# PWM_OUTPUT.net
KiCad netlist of a schematic drawn in Altium Designer
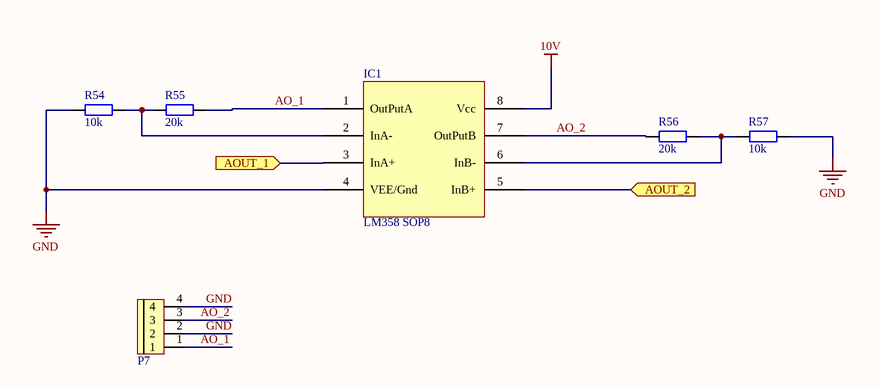
[diagram p0: PWM_OUTPUT.SchDoc]

(export (version "E")
  (design (tool "Eeschema 10.0.6"))
  (components
    (comp (ref "IC1")
      (value "LM358 SOP8")
      (footprint "SOP 8")
      (description "Dán")
      (libsource (lib "Altium_Lib_by_KhueNguyenCreator") (part "LM358 SOP8"))
    )
    (comp (ref "P7")
      (value "CON 4 EDG5.08")
      (footprint "CON 4 4EDG5.08")
      (description "Cắm")
      (libsource (lib "Altium_Lib_by_KhueNguyenCreator") (part "CON 4 EDG5.08"))
    )
    (comp (ref "R54")
      (value "10k")
      (footprint "tro smd 0805")
      (description "Dán")
      (libsource (lib "Altium_Lib_by_KhueNguyenCreator") (part "Tro 0805 5% 10k"))
    )
    (comp (ref "R55")
      (value "20k")
      (footprint "tro smd 0805")
      (description "Dán")
      (libsource (lib "Altium_Lib_by_KhueNguyenCreator") (part "Tro 0805 5% 20k"))
    )
    (comp (ref "R56")
      (value "20k")
      (footprint "tro smd 0805")
      (description "Dán")
      (libsource (lib "Altium_Lib_by_KhueNguyenCreator") (part "Tro 0805 5% 20k"))
    )
    (comp (ref "R57")
      (value "10k")
      (footprint "tro smd 0805")
      (description "Dán")
      (libsource (lib "Altium_Lib_by_KhueNguyenCreator") (part "Tro 0805 5% 10k"))
    )
  )
  (nets
    (net (code "1") (name "/AOUT_1") (class "Default")
      (node (ref "IC1") (pin "3") (pinfunction "InA+_3") (pintype "passive"))
    )
    (net (code "2") (name "/AOUT_2") (class "Default")
      (node (ref "IC1") (pin "5") (pinfunction "InB+_5") (pintype "passive"))
    )
    (net (code "3") (name "/AO_1") (class "Default")
      (node (ref "IC1") (pin "1") (pinfunction "OutPutA_1") (pintype "passive"))
      (node (ref "P7") (pin "1") (pinfunction "1_1") (pintype "passive"))
      (node (ref "R55") (pin "2") (pinfunction "2_2") (pintype "passive"))
    )
    (net (code "4") (name "/AO_2") (class "Default")
      (node (ref "IC1") (pin "7") (pinfunction "OutPutB_7") (pintype "passive"))
      (node (ref "P7") (pin "3") (pinfunction "3_3") (pintype "passive"))
      (node (ref "R56") (pin "1") (pinfunction "1_1") (pintype "passive"))
    )
    (net (code "5") (name "10V") (class "Default")
      (node (ref "IC1") (pin "8") (pinfunction "Vcc_8") (pintype "passive"))
    )
    (net (code "6") (name "GND") (class "Default")
      (node (ref "IC1") (pin "4") (pinfunction "VEE/Gnd_4") (pintype "passive"))
      (node (ref "P7") (pin "2") (pinfunction "2_2") (pintype "passive"))
      (node (ref "P7") (pin "4") (pinfunction "4_4") (pintype "passive"))
      (node (ref "R54") (pin "1") (pinfunction "1_1") (pintype "passive"))
      (node (ref "R57") (pin "2") (pinfunction "2_2") (pintype "passive"))
    )
    (net (code "7") (name "Net-(IC1-InA-)") (class "Default")
      (node (ref "IC1") (pin "2") (pinfunction "InA-_2") (pintype "passive"))
      (node (ref "R54") (pin "2") (pinfunction "2_2") (pintype "passive"))
      (node (ref "R55") (pin "1") (pinfunction "1_1") (pintype "passive"))
    )
    (net (code "8") (name "Net-(IC1-InB-)") (class "Default")
      (node (ref "IC1") (pin "6") (pinfunction "InB-_6") (pintype "passive"))
      (node (ref "R56") (pin "2") (pinfunction "2_2") (pintype "passive"))
      (node (ref "R57") (pin "1") (pinfunction "1_1") (pintype "passive"))
    )
  )
)
